# alimentare.net
KiCad netlist of a schematic drawn in EAGLE
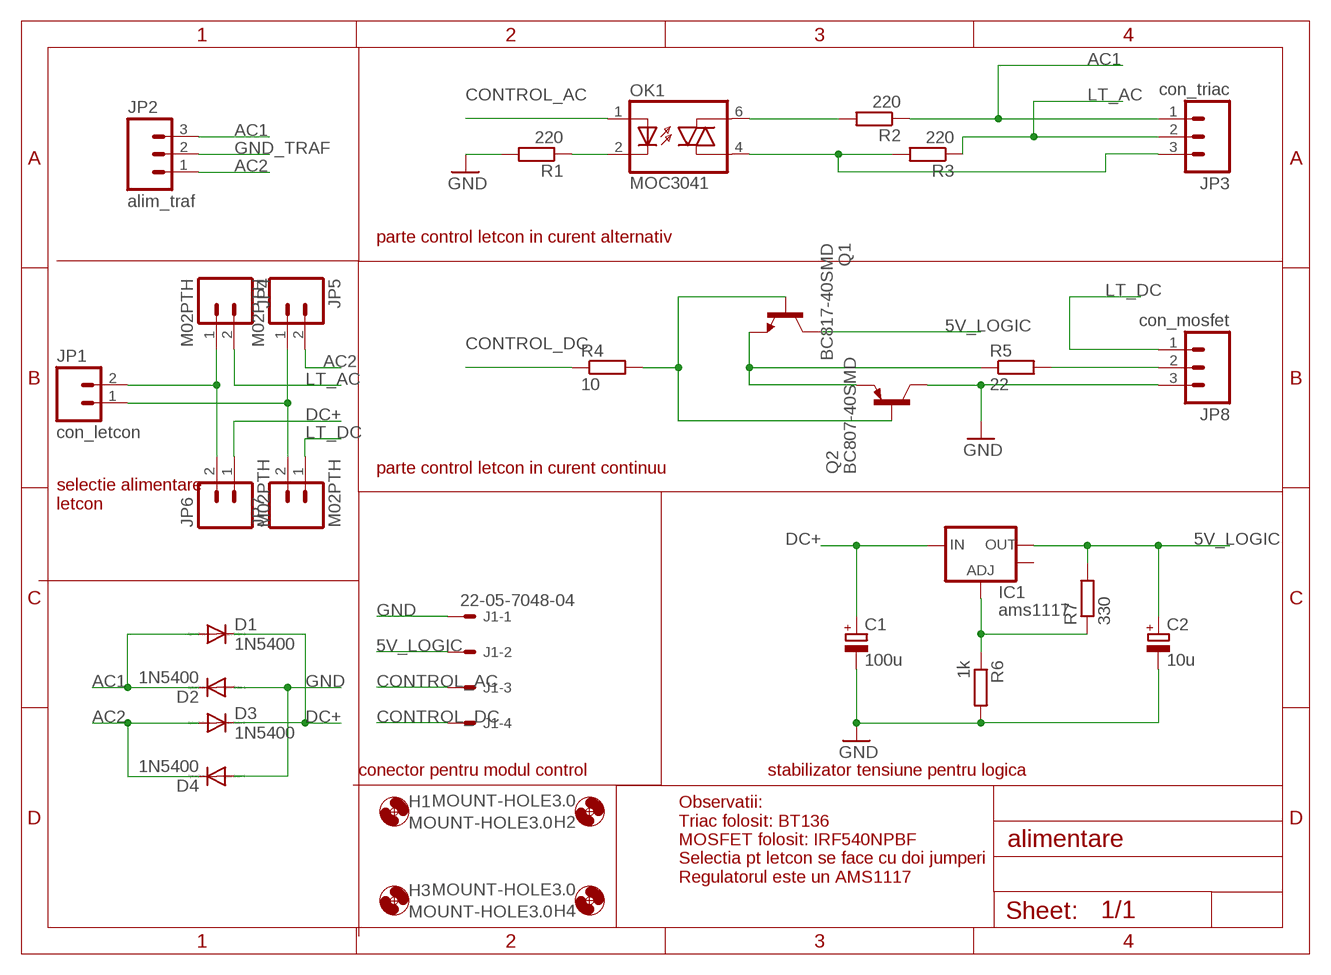
[diagram p0: schematic, sheet 1]

(export (version "E")
  (design (tool "Eeschema 10.0.6"))
  (components
    (comp (ref "C1")
      (value "100u")
      (footprint "eagle-import:E2,5-6E")
      (libsource (lib "eagle-import") (part "CPOL-EUE2,5-6E"))
    )
    (comp (ref "C2")
      (value "10u")
      (footprint "eagle-import:E2,5-6E")
      (libsource (lib "eagle-import") (part "CPOL-EUE2,5-6E"))
    )
    (comp (ref "D1")
      (value "1N5400")
      (footprint "eagle-import:DO201-15")
      (libsource (lib "eagle-import") (part "1N5400"))
    )
    (comp (ref "D2")
      (value "1N5400")
      (footprint "eagle-import:DO201-15")
      (libsource (lib "eagle-import") (part "1N5400"))
    )
    (comp (ref "D3")
      (value "1N5400")
      (footprint "eagle-import:DO201-15")
      (libsource (lib "eagle-import") (part "1N5400"))
    )
    (comp (ref "D4")
      (value "1N5400")
      (footprint "eagle-import:DO201-15")
      (libsource (lib "eagle-import") (part "1N5400"))
    )
    (comp (ref "H1")
      (value "MOUNT-HOLE3.0")
      (footprint "eagle-import:3,0")
      (libsource (lib "eagle-import") (part "MOUNT-HOLE3.0"))
    )
    (comp (ref "H2")
      (value "MOUNT-HOLE3.0")
      (footprint "eagle-import:3,0")
      (libsource (lib "eagle-import") (part "MOUNT-HOLE3.0"))
    )
    (comp (ref "H3")
      (value "MOUNT-HOLE3.0")
      (footprint "eagle-import:3,0")
      (libsource (lib "eagle-import") (part "MOUNT-HOLE3.0"))
    )
    (comp (ref "H4")
      (value "MOUNT-HOLE3.0")
      (footprint "eagle-import:3,0")
      (libsource (lib "eagle-import") (part "MOUNT-HOLE3.0"))
    )
    (comp (ref "IC1")
      (value "ams1117")
      (footprint "eagle-import:SOT223")
      (libsource (lib "eagle-import") (part "V_REG_LM1117SOT223"))
    )
    (comp (ref "J1")
      (value "22-05-7048-04")
      (footprint "eagle-import:7395-04")
      (libsource (lib "eagle-import") (part "22-?-0405-7048"))
    )
    (comp (ref "JP1")
      (value "con_letcon")
      (footprint "eagle-import:SCREWTERMINAL-3.5MM-2")
      (libsource (lib "eagle-import") (part "M023.5MM"))
    )
    (comp (ref "JP2")
      (value "alim_traf")
      (footprint "eagle-import:SCREWTERMINAL-3.5MM-3")
      (libsource (lib "eagle-import") (part "M03SCREW"))
    )
    (comp (ref "JP3")
      (value "con_triac")
      (footprint "eagle-import:MOLEX-1X3")
      (libsource (lib "eagle-import") (part "M03POLAR"))
    )
    (comp (ref "JP4")
      (value "M02PTH")
      (footprint "eagle-import:1X02")
      (libsource (lib "eagle-import") (part "M02PTH"))
    )
    (comp (ref "JP5")
      (value "M02PTH")
      (footprint "eagle-import:1X02")
      (libsource (lib "eagle-import") (part "M02PTH"))
    )
    (comp (ref "JP6")
      (value "M02PTH")
      (footprint "eagle-import:1X02")
      (libsource (lib "eagle-import") (part "M02PTH"))
    )
    (comp (ref "JP7")
      (value "M02PTH")
      (footprint "eagle-import:1X02")
      (libsource (lib "eagle-import") (part "M02PTH"))
    )
    (comp (ref "JP8")
      (value "con_mosfet")
      (footprint "eagle-import:MOLEX-1X3")
      (libsource (lib "eagle-import") (part "M03POLAR"))
    )
    (comp (ref "OK1")
      (value "MOC3041")
      (footprint "eagle-import:DIL06")
      (libsource (lib "eagle-import") (part "MOC3010"))
    )
    (comp (ref "Q1")
      (value "BC817-40SMD")
      (footprint "eagle-import:SOT23-BEC")
      (libsource (lib "eagle-import") (part "BC817SMD-40"))
    )
    (comp (ref "Q2")
      (value "BC807-40SMD")
      (footprint "eagle-import:SOT23-BEC")
      (libsource (lib "eagle-import") (part "BC807SMD-40"))
    )
    (comp (ref "R1")
      (value "220")
      (footprint "eagle-import:M1206")
      (libsource (lib "eagle-import") (part "R-EU_M1206"))
    )
    (comp (ref "R2")
      (value "220")
      (footprint "eagle-import:M1206")
      (libsource (lib "eagle-import") (part "R-EU_M1206"))
    )
    (comp (ref "R3")
      (value "220")
      (footprint "eagle-import:M1206")
      (libsource (lib "eagle-import") (part "R-EU_M1206"))
    )
    (comp (ref "R4")
      (value "10")
      (footprint "eagle-import:M1206")
      (libsource (lib "eagle-import") (part "R-EU_M1206"))
    )
    (comp (ref "R5")
      (value "22")
      (footprint "eagle-import:M1206")
      (libsource (lib "eagle-import") (part "R-EU_M1206"))
    )
    (comp (ref "R6")
      (value "1k")
      (footprint "eagle-import:M1206")
      (libsource (lib "eagle-import") (part "R-EU_M1206"))
    )
    (comp (ref "R7")
      (value "330")
      (footprint "eagle-import:M1206")
      (libsource (lib "eagle-import") (part "R-EU_M1206"))
    )
  )
  (nets
    (net (code "1") (name "/5V_LOGIC") (class "Default")
      (node (ref "C2") (pin "+") (pinfunction "+_+") (pintype "passive"))
      (node (ref "IC1") (pin "2") (pinfunction "OUT_2") (pintype "output"))
      (node (ref "J1") (pin "2") (pinfunction "S_2") (pintype "passive"))
      (node (ref "Q1") (pin "C") (pinfunction "C_C") (pintype "passive"))
      (node (ref "R7") (pin "2") (pinfunction "2_2") (pintype "passive"))
    )
    (net (code "2") (name "/AC1") (class "Default")
      (node (ref "D1") (pin "A") (pinfunction "A_A") (pintype "passive"))
      (node (ref "D2") (pin "C") (pinfunction "C_C") (pintype "passive"))
      (node (ref "JP2") (pin "3") (pinfunction "3_3") (pintype "passive"))
      (node (ref "JP3") (pin "1") (pinfunction "1_1") (pintype "passive"))
      (node (ref "R2") (pin "1") (pinfunction "1_1") (pintype "passive"))
    )
    (net (code "3") (name "/AC2") (class "Default")
      (node (ref "D3") (pin "A") (pinfunction "A_A") (pintype "passive"))
      (node (ref "D4") (pin "C") (pinfunction "C_C") (pintype "passive"))
      (node (ref "JP2") (pin "1") (pinfunction "1_1") (pintype "passive"))
      (node (ref "JP5") (pin "2") (pinfunction "2_2") (pintype "passive"))
    )
    (net (code "4") (name "/CONTROL_AC") (class "Default")
      (node (ref "J1") (pin "3") (pinfunction "S_3") (pintype "passive"))
      (node (ref "OK1") (pin "1") (pinfunction "A_1") (pintype "passive"))
    )
    (net (code "5") (name "/CONTROL_DC") (class "Default")
      (node (ref "J1") (pin "4") (pinfunction "S_4") (pintype "passive"))
      (node (ref "R4") (pin "1") (pinfunction "1_1") (pintype "passive"))
    )
    (net (code "6") (name "/DC+") (class "Default")
      (node (ref "C1") (pin "+") (pinfunction "+_+") (pintype "passive"))
      (node (ref "D1") (pin "C") (pinfunction "C_C") (pintype "passive"))
      (node (ref "D3") (pin "C") (pinfunction "C_C") (pintype "passive"))
      (node (ref "IC1") (pin "3") (pinfunction "IN_3") (pintype "input"))
      (node (ref "JP6") (pin "1") (pinfunction "1_1") (pintype "passive"))
    )
    (net (code "7") (name "/GND_TRAF") (class "Default")
      (node (ref "JP2") (pin "2") (pinfunction "2_2") (pintype "passive"))
    )
    (net (code "8") (name "/LT_AC") (class "Default")
      (node (ref "JP3") (pin "2") (pinfunction "2_2") (pintype "passive"))
      (node (ref "JP4") (pin "2") (pinfunction "2_2") (pintype "passive"))
      (node (ref "R3") (pin "1") (pinfunction "1_1") (pintype "passive"))
    )
    (net (code "9") (name "/LT_DC") (class "Default")
      (node (ref "JP7") (pin "1") (pinfunction "1_1") (pintype "passive"))
      (node (ref "JP8") (pin "1") (pinfunction "1_1") (pintype "passive"))
    )
    (net (code "10") (name "GND") (class "Default")
      (node (ref "C1") (pin "-") (pinfunction "-_-") (pintype "passive"))
      (node (ref "C2") (pin "-") (pinfunction "-_-") (pintype "passive"))
      (node (ref "D2") (pin "A") (pinfunction "A_A") (pintype "passive"))
      (node (ref "D4") (pin "A") (pinfunction "A_A") (pintype "passive"))
      (node (ref "J1") (pin "1") (pinfunction "S_1") (pintype "passive"))
      (node (ref "JP8") (pin "3") (pinfunction "3_3") (pintype "passive"))
      (node (ref "Q2") (pin "C") (pinfunction "C_C") (pintype "passive"))
      (node (ref "R1") (pin "2") (pinfunction "2_2") (pintype "passive"))
      (node (ref "R6") (pin "2") (pinfunction "2_2") (pintype "passive"))
    )
    (net (code "11") (name "Net-(IC1-ADJ)") (class "Default")
      (node (ref "IC1") (pin "1") (pinfunction "ADJ_1") (pintype "input"))
      (node (ref "R6") (pin "1") (pinfunction "1_1") (pintype "passive"))
      (node (ref "R7") (pin "1") (pinfunction "1_1") (pintype "passive"))
    )
    (net (code "12") (name "Net-(JP1-Pad1)") (class "Default")
      (node (ref "JP1") (pin "1") (pinfunction "1_1") (pintype "passive"))
      (node (ref "JP5") (pin "1") (pinfunction "1_1") (pintype "passive"))
      (node (ref "JP7") (pin "2") (pinfunction "2_2") (pintype "passive"))
    )
    (net (code "13") (name "Net-(JP1-Pad2)") (class "Default")
      (node (ref "JP1") (pin "2") (pinfunction "2_2") (pintype "passive"))
      (node (ref "JP4") (pin "1") (pinfunction "1_1") (pintype "passive"))
      (node (ref "JP6") (pin "2") (pinfunction "2_2") (pintype "passive"))
    )
    (net (code "14") (name "Net-(JP8-Pad2)") (class "Default")
      (node (ref "JP8") (pin "2") (pinfunction "2_2") (pintype "passive"))
      (node (ref "R5") (pin "2") (pinfunction "2_2") (pintype "passive"))
    )
    (net (code "15") (name "Net-(OK1-A1)") (class "Default")
      (node (ref "JP3") (pin "3") (pinfunction "3_3") (pintype "passive"))
      (node (ref "OK1") (pin "4") (pinfunction "A1_4") (pintype "passive"))
      (node (ref "R3") (pin "2") (pinfunction "2_2") (pintype "passive"))
    )
    (net (code "16") (name "Net-(OK1-A2)") (class "Default")
      (node (ref "OK1") (pin "6") (pinfunction "A2_6") (pintype "passive"))
      (node (ref "R2") (pin "2") (pinfunction "2_2") (pintype "passive"))
    )
    (net (code "17") (name "Net-(OK1-C)") (class "Default")
      (node (ref "OK1") (pin "2") (pinfunction "C_2") (pintype "passive"))
      (node (ref "R1") (pin "1") (pinfunction "1_1") (pintype "passive"))
    )
    (net (code "18") (name "Net-(Q1-PadB)") (class "Default")
      (node (ref "Q1") (pin "B") (pinfunction "B_B") (pintype "passive"))
      (node (ref "Q2") (pin "B") (pinfunction "B_B") (pintype "passive"))
      (node (ref "R4") (pin "2") (pinfunction "2_2") (pintype "passive"))
    )
    (net (code "19") (name "Net-(Q1-PadE)") (class "Default")
      (node (ref "Q1") (pin "E") (pinfunction "E_E") (pintype "passive"))
      (node (ref "Q2") (pin "E") (pinfunction "E_E") (pintype "passive"))
      (node (ref "R5") (pin "1") (pinfunction "1_1") (pintype "passive"))
    )
    (net (code "20") (name "unconnected-(IC1-OUT-Pad4)") (class "Default")
      (node (ref "IC1") (pin "4") (pinfunction "OUT_4") (pintype "output"))
    )
  )
)
